# Apo_Board_2017_ATmega328.net
KiCad netlist of a schematic drawn in EAGLE
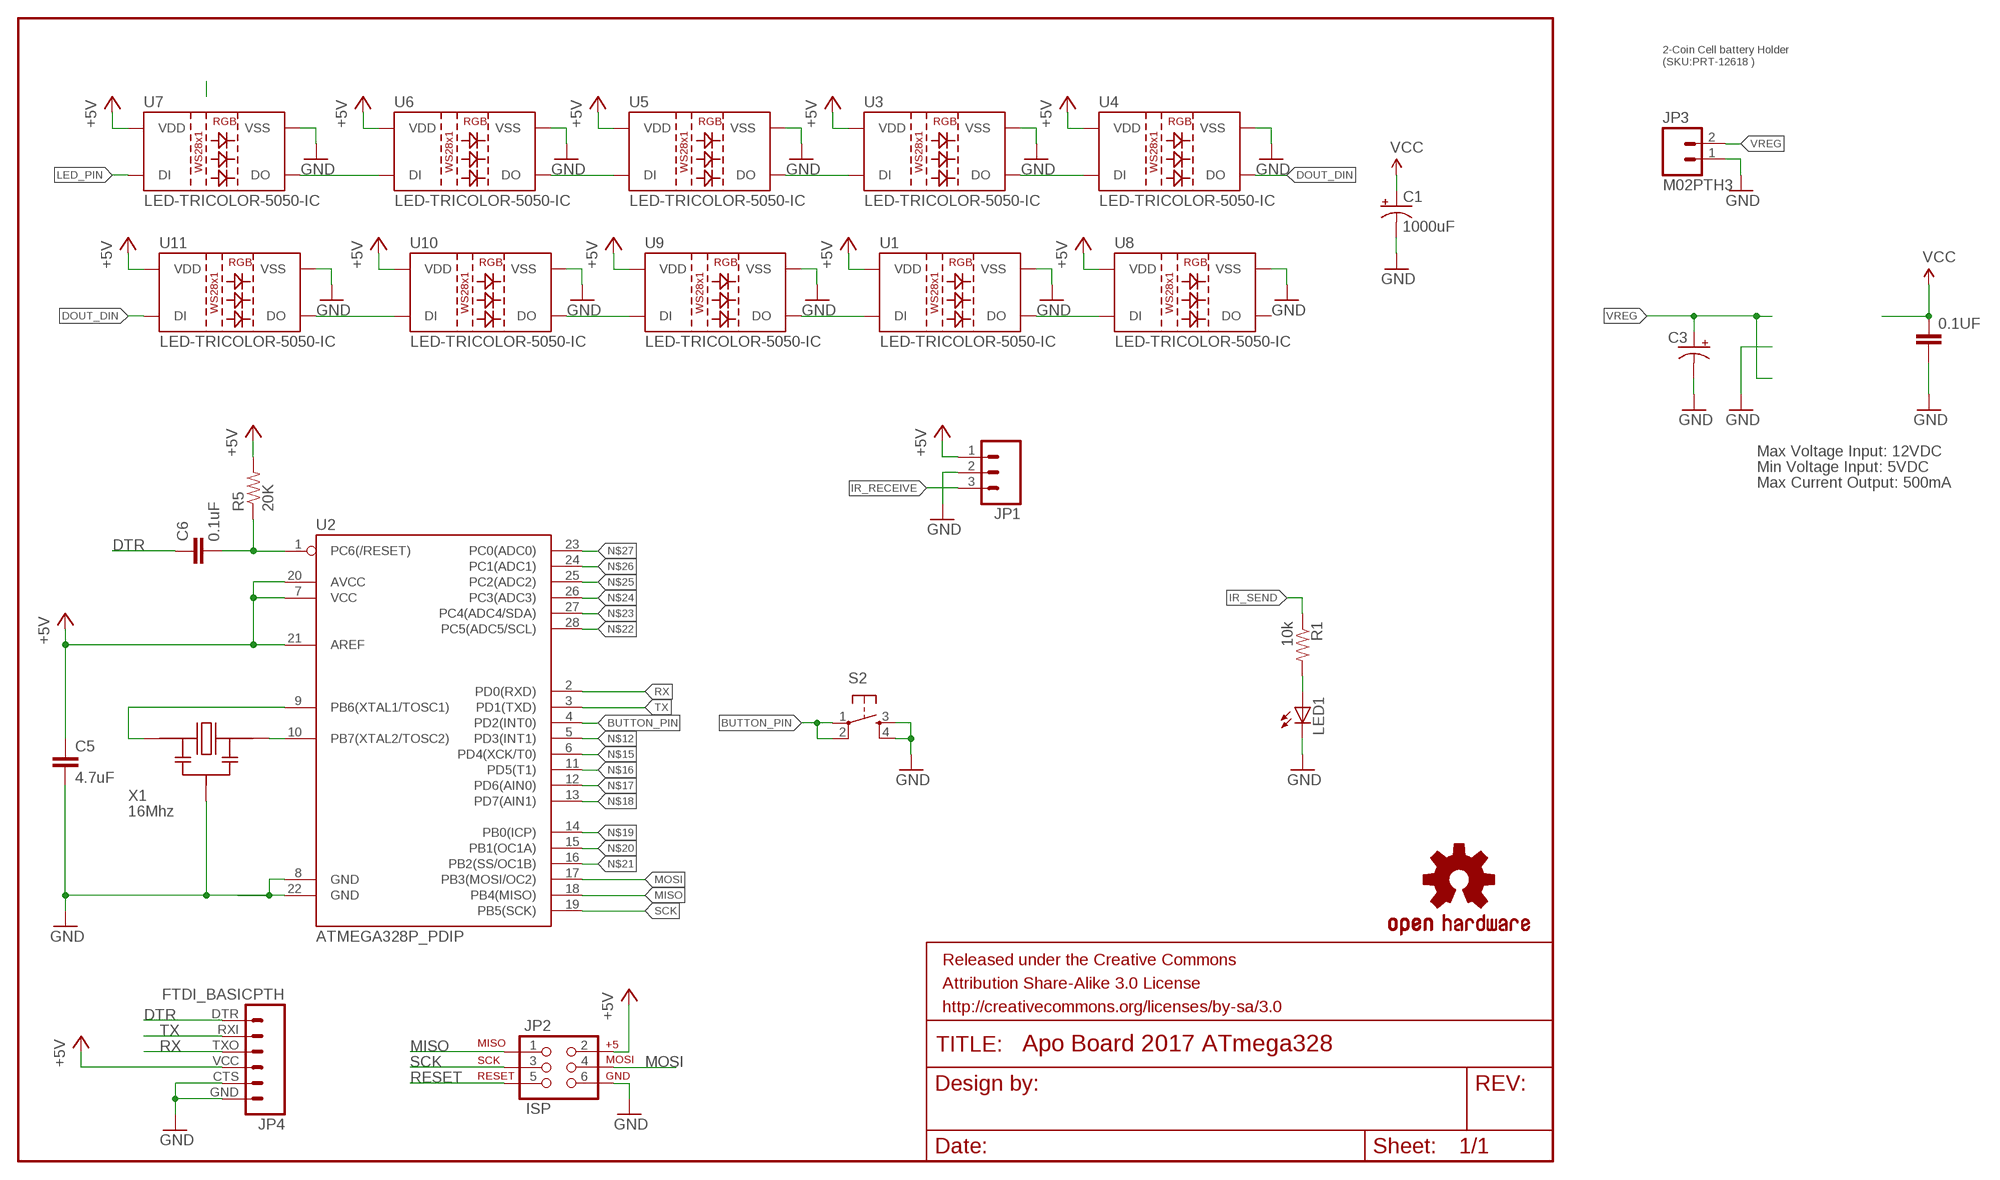
[diagram p0: schematic, sheet 1]

(export (version "E")
  (design (tool "Eeschema 10.0.6"))
  (components
    (comp (ref "0.1UF")
      (value "CAPKIT")
      (footprint "eagle-import:CAP-PTH-SMALL-KIT")
      (libsource (lib "eagle-import") (part "CAPKIT"))
    )
    (comp (ref "C1")
      (value "1000uF")
      (footprint "eagle-import:CPOL-RADIAL-10UF-25V")
      (libsource (lib "eagle-import") (part "CAP_POLPTH2"))
    )
    (comp (ref "C3")
      (value "CAP_POLPTH2")
      (footprint "eagle-import:CPOL-RADIAL-10UF-25V")
      (libsource (lib "eagle-import") (part "CAP_POLPTH2"))
    )
    (comp (ref "C5")
      (value "4.7uF")
      (footprint "eagle-import:CAP-PTH-SMALL-KIT")
      (libsource (lib "eagle-import") (part "SparkFun-Passives_CAPKIT"))
    )
    (comp (ref "C6")
      (value "0.1uF")
      (footprint "eagle-import:CAP-PTH-SMALL-KIT")
      (libsource (lib "eagle-import") (part "SparkFun-Passives_CAPKIT"))
    )
    (comp (ref "FRAME1")
      (value "FRAME-LETTER")
      (footprint "eagle-import:CREATIVE_COMMONS")
      (libsource (lib "eagle-import") (part "FRAME-LETTER"))
    )
    (comp (ref "JP1")
      (value "M03PTH")
      (footprint "eagle-import:1X03")
      (libsource (lib "eagle-import") (part "M03PTH"))
    )
    (comp (ref "JP2")
      (value "ISP")
      (footprint "eagle-import:2X3")
      (libsource (lib "eagle-import") (part "AVR_SPI_PRG_6PTH"))
    )
    (comp (ref "JP3")
      (value "M02PTH3")
      (footprint "eagle-import:1X02_LONGPADS")
      (libsource (lib "eagle-import") (part "M02PTH3"))
    )
    (comp (ref "JP4")
      (value "FTDI_BASICPTH")
      (footprint "eagle-import:FTDI_BASIC")
      (libsource (lib "eagle-import") (part "FTDI_BASICPTH"))
    )
    (comp (ref "LED1")
      (value "LED5MM")
      (footprint "eagle-import:LED5MM")
      (libsource (lib "eagle-import") (part "LED5MM"))
    )
    (comp (ref "LOGO1")
      (value "OSHW-LOGOS")
      (footprint "eagle-import:OSHW-LOGO-S")
      (libsource (lib "eagle-import") (part "OSHW-LOGOS"))
    )
    (comp (ref "R1")
      (value "10k")
      (footprint "eagle-import:AXIAL-0.4")
      (libsource (lib "eagle-import") (part "SparkFun-Resistors_RESISTORPTH-1/4W"))
    )
    (comp (ref "R5")
      (value "20K")
      (footprint "eagle-import:AXIAL-0.3-KIT")
      (libsource (lib "eagle-import") (part "RESISTORKIT"))
    )
    (comp (ref "S2")
      (value "TAC_SWITCHPTH")
      (footprint "eagle-import:TACTILE-PTH")
      (libsource (lib "eagle-import") (part "TAC_SWITCHPTH"))
    )
    (comp (ref "U1")
      (value "LED-TRICOLOR-5050-IC")
      (footprint "eagle-import:LED-RGB-THRU")
      (libsource (lib "eagle-import") (part "LED-TRICOLOR-5050-IC"))
    )
    (comp (ref "U2")
      (value "ATMEGA328P_PDIP")
      (footprint "eagle-import:DIL28-3")
      (libsource (lib "eagle-import") (part "ATMEGA328P_PDIP"))
    )
    (comp (ref "U3")
      (value "LED-TRICOLOR-5050-IC")
      (footprint "eagle-import:LED-RGB-THRU")
      (libsource (lib "eagle-import") (part "LED-TRICOLOR-5050-IC"))
    )
    (comp (ref "U4")
      (value "LED-TRICOLOR-5050-IC")
      (footprint "eagle-import:LED-RGB-THRU")
      (libsource (lib "eagle-import") (part "LED-TRICOLOR-5050-IC"))
    )
    (comp (ref "U5")
      (value "LED-TRICOLOR-5050-IC")
      (footprint "eagle-import:LED-RGB-THRU")
      (libsource (lib "eagle-import") (part "LED-TRICOLOR-5050-IC"))
    )
    (comp (ref "U6")
      (value "LED-TRICOLOR-5050-IC")
      (footprint "eagle-import:LED-RGB-THRU")
      (libsource (lib "eagle-import") (part "LED-TRICOLOR-5050-IC"))
    )
    (comp (ref "U7")
      (value "LED-TRICOLOR-5050-IC")
      (footprint "eagle-import:LED-RGB-THRU")
      (libsource (lib "eagle-import") (part "LED-TRICOLOR-5050-IC"))
    )
    (comp (ref "U8")
      (value "LED-TRICOLOR-5050-IC")
      (footprint "eagle-import:LED-RGB-THRU")
      (libsource (lib "eagle-import") (part "LED-TRICOLOR-5050-IC"))
    )
    (comp (ref "U9")
      (value "LED-TRICOLOR-5050-IC")
      (footprint "eagle-import:LED-RGB-THRU")
      (libsource (lib "eagle-import") (part "LED-TRICOLOR-5050-IC"))
    )
    (comp (ref "U10")
      (value "LED-TRICOLOR-5050-IC")
      (footprint "eagle-import:LED-RGB-THRU")
      (libsource (lib "eagle-import") (part "LED-TRICOLOR-5050-IC"))
    )
    (comp (ref "U11")
      (value "LED-TRICOLOR-5050-IC")
      (footprint "eagle-import:LED-RGB-THRU")
      (libsource (lib "eagle-import") (part "LED-TRICOLOR-5050-IC"))
    )
    (comp (ref "X1")
      (value "16Mhz")
      (footprint "eagle-import:CERAMIC_RESONATOR_ZTT")
      (libsource (lib "eagle-import") (part "CERAMIC_RESONATOR"))
    )
  )
  (nets
    (net (code "1") (name "+5V") (class "Default")
      (node (ref "C5") (pin "1") (pinfunction "1_1") (pintype "passive"))
      (node (ref "JP1") (pin "1") (pinfunction "1_1") (pintype "passive"))
      (node (ref "JP2") (pin "2") (pinfunction "2_2") (pintype "passive"))
      (node (ref "JP4") (pin "VCC") (pinfunction "4_VCC") (pintype "passive"))
      (node (ref "R5") (pin "P$2") (pinfunction "2_P$2") (pintype "passive"))
      (node (ref "U1") (pin "2") (pinfunction "VDD_2") (pintype "bidirectional"))
      (node (ref "U10") (pin "2") (pinfunction "VDD_2") (pintype "bidirectional"))
      (node (ref "U11") (pin "2") (pinfunction "VDD_2") (pintype "bidirectional"))
      (node (ref "U2") (pin "20") (pinfunction "AVCC_20") (pintype "bidirectional"))
      (node (ref "U2") (pin "21") (pinfunction "AREF_21") (pintype "bidirectional"))
      (node (ref "U2") (pin "7") (pinfunction "VCC_7") (pintype "bidirectional"))
      (node (ref "U3") (pin "2") (pinfunction "VDD_2") (pintype "bidirectional"))
      (node (ref "U4") (pin "2") (pinfunction "VDD_2") (pintype "bidirectional"))
      (node (ref "U5") (pin "2") (pinfunction "VDD_2") (pintype "bidirectional"))
      (node (ref "U6") (pin "2") (pinfunction "VDD_2") (pintype "bidirectional"))
      (node (ref "U7") (pin "2") (pinfunction "VDD_2") (pintype "bidirectional"))
      (node (ref "U8") (pin "2") (pinfunction "VDD_2") (pintype "bidirectional"))
      (node (ref "U9") (pin "2") (pinfunction "VDD_2") (pintype "bidirectional"))
    )
    (net (code "2") (name "/DTR") (class "Default")
      (node (ref "C6") (pin "1") (pinfunction "1_1") (pintype "passive"))
      (node (ref "JP4") (pin "DTR") (pinfunction "1_DTR") (pintype "passive"))
    )
    (net (code "3") (name "/RESET") (class "Default")
      (node (ref "JP2") (pin "5") (pinfunction "5_5") (pintype "passive"))
    )
    (net (code "4") (name "BUTTON_PIN") (class "Default")
      (node (ref "S2") (pin "1") (pinfunction "1_1") (pintype "passive"))
      (node (ref "S2") (pin "2") (pinfunction "2_2") (pintype "passive"))
      (node (ref "U2") (pin "4") (pinfunction "PD2(INT0)_4") (pintype "bidirectional"))
    )
    (net (code "5") (name "DOUT_DIN") (class "Default")
      (node (ref "U11") (pin "1") (pinfunction "DI_1") (pintype "bidirectional"))
      (node (ref "U4") (pin "4") (pinfunction "DO_4") (pintype "bidirectional"))
    )
    (net (code "6") (name "GND") (class "Default")
      (node (ref "0.1UF") (pin "2") (pinfunction "2_2") (pintype "passive"))
      (node (ref "C1") (pin "2") (pinfunction "-_2") (pintype "passive"))
      (node (ref "C3") (pin "2") (pinfunction "-_2") (pintype "passive"))
      (node (ref "C5") (pin "2") (pinfunction "2_2") (pintype "passive"))
      (node (ref "JP1") (pin "2") (pinfunction "2_2") (pintype "passive"))
      (node (ref "JP2") (pin "6") (pinfunction "6_6") (pintype "passive"))
      (node (ref "JP3") (pin "1") (pinfunction "1_1") (pintype "passive"))
      (node (ref "JP4") (pin "CTS") (pinfunction "5_CTS") (pintype "passive"))
      (node (ref "JP4") (pin "GND") (pinfunction "6_GND") (pintype "passive"))
      (node (ref "LED1") (pin "K") (pinfunction "C_K") (pintype "passive"))
      (node (ref "S2") (pin "3") (pinfunction "3_3") (pintype "passive"))
      (node (ref "S2") (pin "4") (pinfunction "4_4") (pintype "passive"))
      (node (ref "U1") (pin "3") (pinfunction "VSS_3") (pintype "bidirectional"))
      (node (ref "U10") (pin "3") (pinfunction "VSS_3") (pintype "bidirectional"))
      (node (ref "U11") (pin "3") (pinfunction "VSS_3") (pintype "bidirectional"))
      (node (ref "U2") (pin "22") (pinfunction "GND_22") (pintype "bidirectional"))
      (node (ref "U2") (pin "8") (pinfunction "GND_8") (pintype "bidirectional"))
      (node (ref "U3") (pin "3") (pinfunction "VSS_3") (pintype "bidirectional"))
      (node (ref "U4") (pin "3") (pinfunction "VSS_3") (pintype "bidirectional"))
      (node (ref "U5") (pin "3") (pinfunction "VSS_3") (pintype "bidirectional"))
      (node (ref "U6") (pin "3") (pinfunction "VSS_3") (pintype "bidirectional"))
      (node (ref "U7") (pin "3") (pinfunction "VSS_3") (pintype "bidirectional"))
      (node (ref "U8") (pin "3") (pinfunction "VSS_3") (pintype "bidirectional"))
      (node (ref "U9") (pin "3") (pinfunction "VSS_3") (pintype "bidirectional"))
      (node (ref "X1") (pin "P$2") (pinfunction "P$2_P$2") (pintype "bidirectional"))
    )
    (net (code "7") (name "IR_RECEIVE") (class "Default")
      (node (ref "JP1") (pin "3") (pinfunction "3_3") (pintype "passive"))
    )
    (net (code "8") (name "IR_SEND") (class "Default")
      (node (ref "R1") (pin "P$1") (pinfunction "1_P$1") (pintype "passive"))
    )
    (net (code "9") (name "LED_PIN") (class "Default")
      (node (ref "U7") (pin "1") (pinfunction "DI_1") (pintype "bidirectional"))
    )
    (net (code "10") (name "MISO") (class "Default")
      (node (ref "JP2") (pin "1") (pinfunction "1_1") (pintype "passive"))
      (node (ref "U2") (pin "18") (pinfunction "PB4(MISO)_18") (pintype "bidirectional"))
    )
    (net (code "11") (name "MOSI") (class "Default")
      (node (ref "JP2") (pin "4") (pinfunction "4_4") (pintype "passive"))
      (node (ref "U2") (pin "17") (pinfunction "PB3(MOSI/OC2)_17") (pintype "bidirectional"))
    )
    (net (code "12") (name "N$12") (class "Default")
      (node (ref "U2") (pin "5") (pinfunction "PD3(INT1)_5") (pintype "bidirectional"))
    )
    (net (code "13") (name "N$15") (class "Default")
      (node (ref "U2") (pin "6") (pinfunction "PD4(XCK/T0)_6") (pintype "bidirectional"))
    )
    (net (code "14") (name "N$16") (class "Default")
      (node (ref "U2") (pin "11") (pinfunction "PD5(T1)_11") (pintype "bidirectional"))
    )
    (net (code "15") (name "N$17") (class "Default")
      (node (ref "U2") (pin "12") (pinfunction "PD6(AIN0)_12") (pintype "bidirectional"))
    )
    (net (code "16") (name "N$18") (class "Default")
      (node (ref "U2") (pin "13") (pinfunction "PD7(AIN1)_13") (pintype "bidirectional"))
    )
    (net (code "17") (name "N$19") (class "Default")
      (node (ref "U2") (pin "14") (pinfunction "PB0(ICP)_14") (pintype "bidirectional"))
    )
    (net (code "18") (name "N$20") (class "Default")
      (node (ref "U2") (pin "15") (pinfunction "PB1(OC1A)_15") (pintype "bidirectional"))
    )
    (net (code "19") (name "N$21") (class "Default")
      (node (ref "U2") (pin "16") (pinfunction "PB2(SS/OC1B)_16") (pintype "bidirectional"))
    )
    (net (code "20") (name "N$22") (class "Default")
      (node (ref "U2") (pin "28") (pinfunction "PC5(ADC5/SCL)_28") (pintype "bidirectional"))
    )
    (net (code "21") (name "N$23") (class "Default")
      (node (ref "U2") (pin "27") (pinfunction "PC4(ADC4/SDA)_27") (pintype "bidirectional"))
    )
    (net (code "22") (name "N$24") (class "Default")
      (node (ref "U2") (pin "26") (pinfunction "PC3(ADC3)_26") (pintype "bidirectional"))
    )
    (net (code "23") (name "N$25") (class "Default")
      (node (ref "U2") (pin "25") (pinfunction "PC2(ADC2)_25") (pintype "bidirectional"))
    )
    (net (code "24") (name "N$26") (class "Default")
      (node (ref "U2") (pin "24") (pinfunction "PC1(ADC1)_24") (pintype "bidirectional"))
    )
    (net (code "25") (name "N$27") (class "Default")
      (node (ref "U2") (pin "23") (pinfunction "PC0(ADC0)_23") (pintype "bidirectional"))
    )
    (net (code "26") (name "Net-(R1-2)") (class "Default")
      (node (ref "LED1") (pin "A") (pinfunction "A_A") (pintype "passive"))
      (node (ref "R1") (pin "P$2") (pinfunction "2_P$2") (pintype "passive"))
    )
    (net (code "27") (name "Net-(R5-1)") (class "Default")
      (node (ref "C6") (pin "2") (pinfunction "2_2") (pintype "passive"))
      (node (ref "R5") (pin "P$1") (pinfunction "1_P$1") (pintype "passive"))
      (node (ref "U2") (pin "1") (pinfunction "PC6(/RESET)_1") (pintype "bidirectional"))
    )
    (net (code "28") (name "Net-(U1-DI)") (class "Default")
      (node (ref "U1") (pin "1") (pinfunction "DI_1") (pintype "bidirectional"))
      (node (ref "U9") (pin "4") (pinfunction "DO_4") (pintype "bidirectional"))
    )
    (net (code "29") (name "Net-(U1-DO)") (class "Default")
      (node (ref "U1") (pin "4") (pinfunction "DO_4") (pintype "bidirectional"))
      (node (ref "U8") (pin "1") (pinfunction "DI_1") (pintype "bidirectional"))
    )
    (net (code "30") (name "Net-(U2-PB6(XTAL1{slash}TOSC1))") (class "Default")
      (node (ref "U2") (pin "9") (pinfunction "PB6(XTAL1/TOSC1)_9") (pintype "bidirectional"))
      (node (ref "X1") (pin "P$1") (pinfunction "P$1_P$1") (pintype "bidirectional"))
    )
    (net (code "31") (name "Net-(U2-PB7(XTAL2{slash}TOSC2))") (class "Default")
      (node (ref "U2") (pin "10") (pinfunction "PB7(XTAL2/TOSC2)_10") (pintype "bidirectional"))
      (node (ref "X1") (pin "P$3") (pinfunction "P$3_P$3") (pintype "bidirectional"))
    )
    (net (code "32") (name "Net-(U3-DI)") (class "Default")
      (node (ref "U3") (pin "1") (pinfunction "DI_1") (pintype "bidirectional"))
      (node (ref "U5") (pin "4") (pinfunction "DO_4") (pintype "bidirectional"))
    )
    (net (code "33") (name "Net-(U3-DO)") (class "Default")
      (node (ref "U3") (pin "4") (pinfunction "DO_4") (pintype "bidirectional"))
      (node (ref "U4") (pin "1") (pinfunction "DI_1") (pintype "bidirectional"))
    )
    (net (code "34") (name "Net-(U5-DI)") (class "Default")
      (node (ref "U5") (pin "1") (pinfunction "DI_1") (pintype "bidirectional"))
      (node (ref "U6") (pin "4") (pinfunction "DO_4") (pintype "bidirectional"))
    )
    (net (code "35") (name "Net-(U6-DI)") (class "Default")
      (node (ref "U6") (pin "1") (pinfunction "DI_1") (pintype "bidirectional"))
      (node (ref "U7") (pin "4") (pinfunction "DO_4") (pintype "bidirectional"))
    )
    (net (code "36") (name "Net-(U10-DI)") (class "Default")
      (node (ref "U10") (pin "1") (pinfunction "DI_1") (pintype "bidirectional"))
      (node (ref "U11") (pin "4") (pinfunction "DO_4") (pintype "bidirectional"))
    )
    (net (code "37") (name "Net-(U10-DO)") (class "Default")
      (node (ref "U10") (pin "4") (pinfunction "DO_4") (pintype "bidirectional"))
      (node (ref "U9") (pin "1") (pinfunction "DI_1") (pintype "bidirectional"))
    )
    (net (code "38") (name "RX") (class "Default")
      (node (ref "JP4") (pin "TXO") (pinfunction "3_TXO") (pintype "passive"))
      (node (ref "U2") (pin "2") (pinfunction "PD0(RXD)_2") (pintype "bidirectional"))
    )
    (net (code "39") (name "SCK") (class "Default")
      (node (ref "JP2") (pin "3") (pinfunction "3_3") (pintype "passive"))
      (node (ref "U2") (pin "19") (pinfunction "PB5(SCK)_19") (pintype "bidirectional"))
    )
    (net (code "40") (name "TX") (class "Default")
      (node (ref "JP4") (pin "RXI") (pinfunction "2_RXI") (pintype "passive"))
      (node (ref "U2") (pin "3") (pinfunction "PD1(TXD)_3") (pintype "bidirectional"))
    )
    (net (code "41") (name "VCC") (class "Default")
      (node (ref "0.1UF") (pin "1") (pinfunction "1_1") (pintype "passive"))
      (node (ref "C1") (pin "1") (pinfunction "+_1") (pintype "passive"))
    )
    (net (code "42") (name "VREG") (class "Default")
      (node (ref "C3") (pin "1") (pinfunction "+_1") (pintype "passive"))
      (node (ref "JP3") (pin "2") (pinfunction "2_2") (pintype "passive"))
    )
    (net (code "43") (name "unconnected-(U8-DO-Pad4)") (class "Default")
      (node (ref "U8") (pin "4") (pinfunction "DO_4") (pintype "bidirectional"))
    )
  )
)
